# breakout.net
KiCad netlist of a schematic drawn in EAGLE
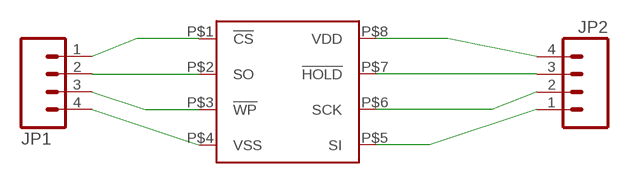
[diagram p0: schematic, sheet 1]

(export (version "E")
  (design (tool "Eeschema 10.0.6"))
  (components
    (comp (ref "JP1")
      (value "M04PTH")
      (footprint "eagle-import:1X04")
      (libsource (lib "eagle-import") (part "M04PTH"))
    )
    (comp (ref "JP2")
      (value "M04PTH")
      (footprint "eagle-import:1X04")
      (libsource (lib "eagle-import") (part "M04PTH"))
    )
    (comp (ref "U$1")
      (value "MR25H256")
      (footprint "eagle-import:DFN8")
      (libsource (lib "eagle-import") (part "MR25H256"))
    )
  )
  (nets
    (net (code "1") (name "Net-(U$1-SCK)") (class "Default")
      (node (ref "JP2") (pin "2") (pinfunction "2_2") (pintype "passive"))
      (node (ref "U$1") (pin "P$6") (pinfunction "SCK_P$6") (pintype "input"))
    )
    (net (code "2") (name "Net-(U$1-SI)") (class "Default")
      (node (ref "JP2") (pin "1") (pinfunction "1_1") (pintype "passive"))
      (node (ref "U$1") (pin "P$5") (pinfunction "SI_P$5") (pintype "input"))
    )
    (net (code "3") (name "Net-(U$1-SO)") (class "Default")
      (node (ref "JP1") (pin "2") (pinfunction "2_2") (pintype "passive"))
      (node (ref "U$1") (pin "P$2") (pinfunction "SO_P$2") (pintype "input"))
    )
    (net (code "4") (name "Net-(U$1-VDD)") (class "Default")
      (node (ref "JP2") (pin "4") (pinfunction "4_4") (pintype "passive"))
      (node (ref "U$1") (pin "P$8") (pinfunction "VDD_P$8") (pintype "input"))
    )
    (net (code "5") (name "Net-(U$1-VSS)") (class "Default")
      (node (ref "JP1") (pin "4") (pinfunction "4_4") (pintype "passive"))
      (node (ref "U$1") (pin "P$4") (pinfunction "VSS_P$4") (pintype "input"))
    )
    (net (code "6") (name "Net-(U$1-~{CS})") (class "Default")
      (node (ref "JP1") (pin "1") (pinfunction "1_1") (pintype "passive"))
      (node (ref "U$1") (pin "P$1") (pinfunction "~{CS}_P$1") (pintype "input"))
    )
    (net (code "7") (name "Net-(U$1-~{HOLD})") (class "Default")
      (node (ref "JP2") (pin "3") (pinfunction "3_3") (pintype "passive"))
      (node (ref "U$1") (pin "P$7") (pinfunction "~{HOLD}_P$7") (pintype "input"))
    )
    (net (code "8") (name "Net-(U$1-~{WP})") (class "Default")
      (node (ref "JP1") (pin "3") (pinfunction "3_3") (pintype "passive"))
      (node (ref "U$1") (pin "P$3") (pinfunction "~{WP}_P$3") (pintype "input"))
    )
  )
)
